# SCH__LM324_2022-09-28.net
KiCad netlist of a schematic drawn in EasyEDA
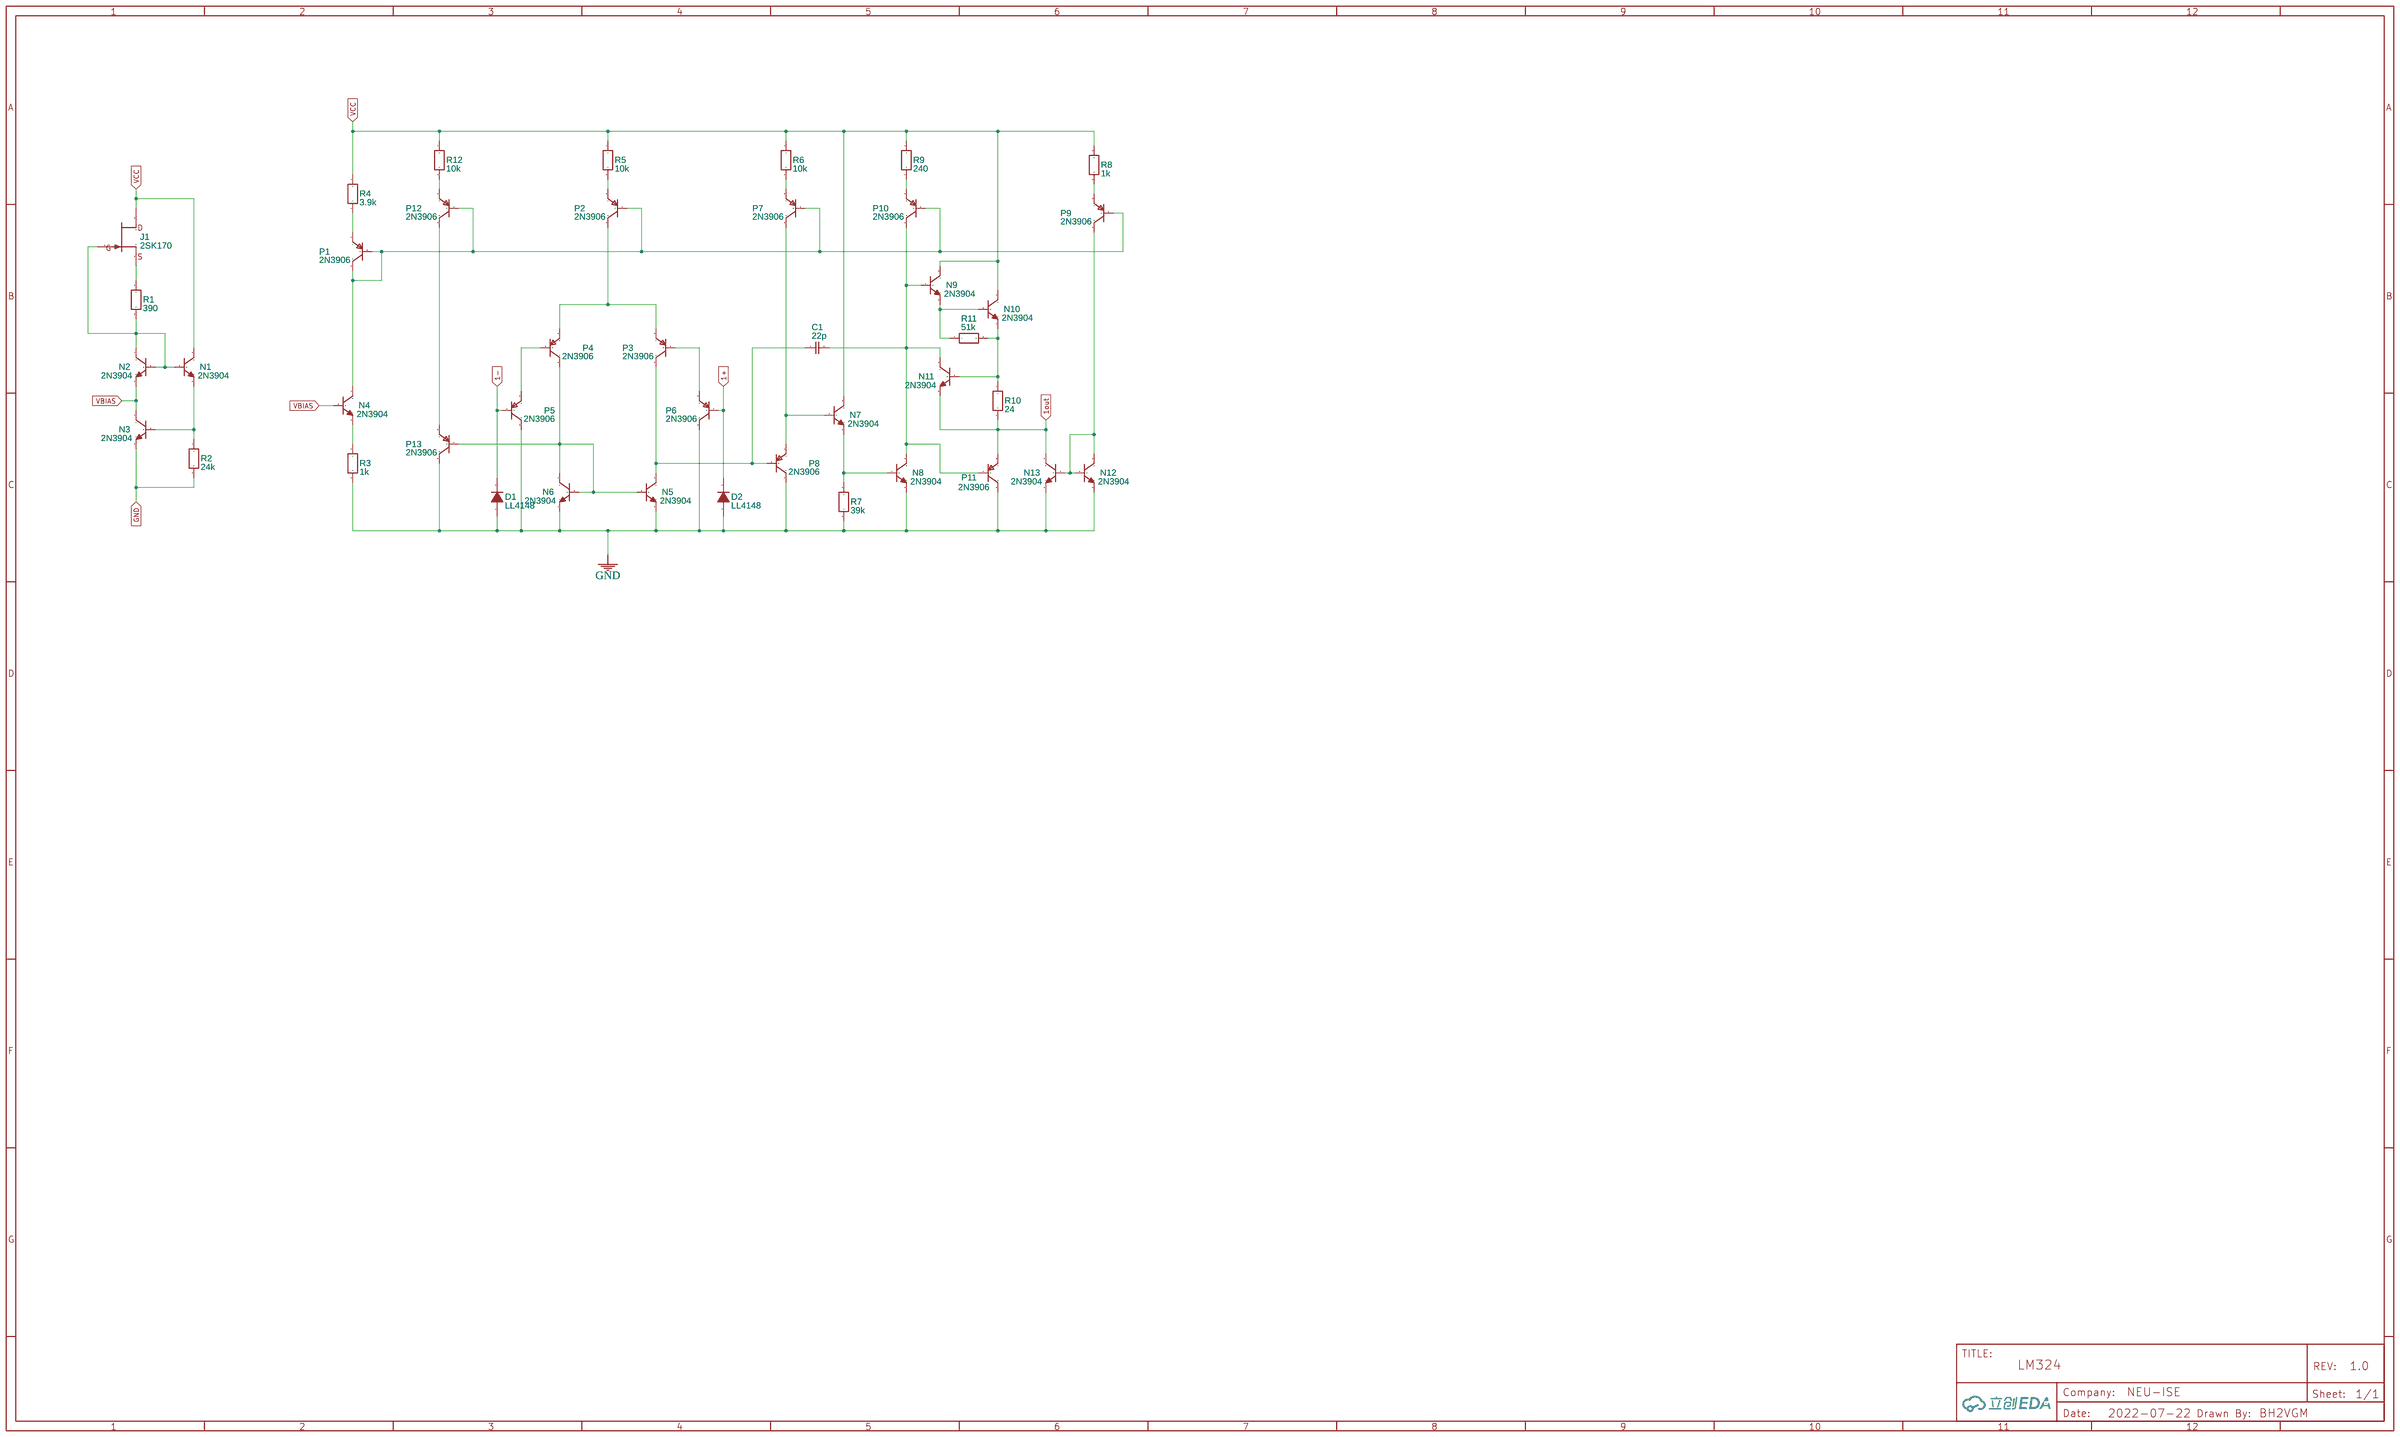
[diagram p0: schematic sheet]

(export (version "E")
  (design (tool "Eeschema 10.0.6"))
  (components
    (comp (ref "C1") (value "22p") (libsource (lib "") (part "独石电容 5.08mm")))
    (comp (ref "D1")
      (value "LL4148")
      (fields
        (field (name "BOM_Manufacturer Part") "LL4148-GS08")
        (field (name "BOM_Supplier Part") "C68883")
      )
      (libsource (lib "") (part "LL4148"))
    )
    (comp (ref "D2")
      (value "LL4148")
      (fields
        (field (name "BOM_Manufacturer Part") "LL4148-GS08")
        (field (name "BOM_Supplier Part") "C68883")
      )
      (libsource (lib "") (part "LL4148"))
    )
    (comp (ref "J1") (value "2SK170") (libsource (lib "") (part "2SK170")))
    (comp (ref "N1")
      (value "2N3904")
      (fields (field (name "BOM_Supplier Part") "C118538"))
      (libsource (lib "") (part "2N3904_1"))
    )
    (comp (ref "N2")
      (value "2N3904")
      (fields (field (name "BOM_Supplier Part") "C118538"))
      (libsource (lib "") (part "2N3904"))
    )
    (comp (ref "N3")
      (value "2N3904")
      (fields (field (name "BOM_Supplier Part") "C118538"))
      (libsource (lib "") (part "2N3904"))
    )
    (comp (ref "N4")
      (value "2N3904")
      (fields (field (name "BOM_Supplier Part") "C118538"))
      (libsource (lib "") (part "2N3904_1"))
    )
    (comp (ref "N5")
      (value "2N3904")
      (fields (field (name "BOM_Supplier Part") "C118538"))
      (libsource (lib "") (part "2N3904_1"))
    )
    (comp (ref "N6")
      (value "2N3904")
      (fields (field (name "BOM_Supplier Part") "C118538"))
      (libsource (lib "") (part "2N3904"))
    )
    (comp (ref "N7")
      (value "2N3904")
      (fields (field (name "BOM_Supplier Part") "C118538"))
      (libsource (lib "") (part "2N3904_1"))
    )
    (comp (ref "N8")
      (value "2N3904")
      (fields (field (name "BOM_Supplier Part") "C118538"))
      (libsource (lib "") (part "2N3904_1"))
    )
    (comp (ref "N9")
      (value "2N3904")
      (fields (field (name "BOM_Supplier Part") "C118538"))
      (libsource (lib "") (part "2N3904_1"))
    )
    (comp (ref "N10")
      (value "2N3904")
      (fields (field (name "BOM_Supplier Part") "C118538"))
      (libsource (lib "") (part "2N3904_1"))
    )
    (comp (ref "N11")
      (value "2N3904")
      (fields (field (name "BOM_Supplier Part") "C118538"))
      (libsource (lib "") (part "2N3904"))
    )
    (comp (ref "N12")
      (value "2N3904")
      (fields (field (name "BOM_Supplier Part") "C118538"))
      (libsource (lib "") (part "2N3904_1"))
    )
    (comp (ref "N13")
      (value "2N3904")
      (fields (field (name "BOM_Supplier Part") "C118538"))
      (libsource (lib "") (part "2N3904"))
    )
    (comp (ref "P1")
      (value "2N3906")
      (fields (field (name "BOM_Supplier Part") "C9809"))
      (libsource (lib "") (part "2N3906_1"))
    )
    (comp (ref "P2")
      (value "2N3906")
      (fields (field (name "BOM_Supplier Part") "C9809"))
      (libsource (lib "") (part "2N3906_1"))
    )
    (comp (ref "P3")
      (value "2N3906")
      (fields (field (name "BOM_Supplier Part") "C9809"))
      (libsource (lib "") (part "2N3906_1"))
    )
    (comp (ref "P4")
      (value "2N3906")
      (fields (field (name "BOM_Supplier Part") "C9809"))
      (libsource (lib "") (part "2N3906"))
    )
    (comp (ref "P5")
      (value "2N3906")
      (fields (field (name "BOM_Supplier Part") "C9809"))
      (libsource (lib "") (part "2N3906"))
    )
    (comp (ref "P6")
      (value "2N3906")
      (fields (field (name "BOM_Supplier Part") "C9809"))
      (libsource (lib "") (part "2N3906_1"))
    )
    (comp (ref "P7")
      (value "2N3906")
      (fields (field (name "BOM_Supplier Part") "C9809"))
      (libsource (lib "") (part "2N3906_1"))
    )
    (comp (ref "P8")
      (value "2N3906")
      (fields (field (name "BOM_Supplier Part") "C9809"))
      (libsource (lib "") (part "2N3906"))
    )
    (comp (ref "P9")
      (value "2N3906")
      (fields (field (name "BOM_Supplier Part") "C9809"))
      (libsource (lib "") (part "2N3906_1"))
    )
    (comp (ref "P10")
      (value "2N3906")
      (fields (field (name "BOM_Supplier Part") "C9809"))
      (libsource (lib "") (part "2N3906_1"))
    )
    (comp (ref "P11")
      (value "2N3906")
      (fields (field (name "BOM_Supplier Part") "C9809"))
      (libsource (lib "") (part "2N3906"))
    )
    (comp (ref "P12")
      (value "2N3906")
      (fields (field (name "BOM_Supplier Part") "C9809"))
      (libsource (lib "") (part "2N3906_1"))
    )
    (comp (ref "P13")
      (value "2N3906")
      (fields (field (name "BOM_Supplier Part") "C9809"))
      (libsource (lib "") (part "2N3906_1"))
    )
    (comp (ref "R1") (value "390") (libsource (lib "") (part "1/4W电阻")))
    (comp (ref "R2") (value "24k") (libsource (lib "") (part "1/4W电阻")))
    (comp (ref "R3") (value "1k") (libsource (lib "") (part "1/4W电阻")))
    (comp (ref "R4") (value "3.9k") (libsource (lib "") (part "1/4W电阻")))
    (comp (ref "R5") (value "10k") (libsource (lib "") (part "1/4W电阻")))
    (comp (ref "R6") (value "10k") (libsource (lib "") (part "1/4W电阻")))
    (comp (ref "R7") (value "39k") (libsource (lib "") (part "1/4W电阻")))
    (comp (ref "R8") (value "1k") (libsource (lib "") (part "1/4W电阻")))
    (comp (ref "R9") (value "240") (libsource (lib "") (part "1/4W电阻")))
    (comp (ref "R10") (value "24") (libsource (lib "") (part "1/4W电阻")))
    (comp (ref "R11") (value "51k") (libsource (lib "") (part "1/4W电阻_1")))
    (comp (ref "R12") (value "10k") (libsource (lib "") (part "1/4W电阻")))
  )
  (nets
    (net (code "1") (name "1+") (class "Default")
      (node (ref "D2") (pin "1") (pinfunction "C_1") (pintype "unspecified"))
      (node (ref "P6") (pin "b") (pinfunction "B_b") (pintype "unspecified"))
    )
    (net (code "2") (name "1-") (class "Default")
      (node (ref "D1") (pin "1") (pinfunction "C_1") (pintype "unspecified"))
      (node (ref "P5") (pin "b") (pinfunction "B_b") (pintype "unspecified"))
    )
    (net (code "3") (name "1out") (class "Default")
      (node (ref "N11") (pin "e") (pinfunction "E_e") (pintype "unspecified"))
      (node (ref "N13") (pin "c") (pinfunction "C_c") (pintype "unspecified"))
      (node (ref "P11") (pin "e") (pinfunction "E_e") (pintype "unspecified"))
      (node (ref "R10") (pin "2") (pinfunction "2_2") (pintype "unspecified"))
    )
    (net (code "4") (name "GND") (class "Default")
      (node (ref "D1") (pin "2") (pinfunction "A_2") (pintype "unspecified"))
      (node (ref "D2") (pin "2") (pinfunction "A_2") (pintype "unspecified"))
      (node (ref "N12") (pin "e") (pinfunction "E_e") (pintype "unspecified"))
      (node (ref "N13") (pin "e") (pinfunction "E_e") (pintype "unspecified"))
      (node (ref "N3") (pin "e") (pinfunction "E_e") (pintype "unspecified"))
      (node (ref "N5") (pin "e") (pinfunction "E_e") (pintype "unspecified"))
      (node (ref "N6") (pin "e") (pinfunction "E_e") (pintype "unspecified"))
      (node (ref "N8") (pin "e") (pinfunction "E_e") (pintype "unspecified"))
      (node (ref "P11") (pin "c") (pinfunction "C_c") (pintype "unspecified"))
      (node (ref "P13") (pin "c") (pinfunction "C_c") (pintype "unspecified"))
      (node (ref "P5") (pin "c") (pinfunction "C_c") (pintype "unspecified"))
      (node (ref "P6") (pin "c") (pinfunction "C_c") (pintype "unspecified"))
      (node (ref "P8") (pin "c") (pinfunction "C_c") (pintype "unspecified"))
      (node (ref "R2") (pin "2") (pinfunction "2_2") (pintype "unspecified"))
      (node (ref "R3") (pin "2") (pinfunction "2_2") (pintype "unspecified"))
      (node (ref "R7") (pin "2") (pinfunction "2_2") (pintype "unspecified"))
    )
    (net (code "5") (name "Net-(J1-G)") (class "Default")
      (node (ref "J1") (pin "2") (pinfunction "G_2") (pintype "unspecified"))
      (node (ref "N1") (pin "b") (pinfunction "B_b") (pintype "unspecified"))
      (node (ref "N2") (pin "b") (pinfunction "B_b") (pintype "unspecified"))
      (node (ref "N2") (pin "c") (pinfunction "C_c") (pintype "unspecified"))
      (node (ref "R1") (pin "2") (pinfunction "2_2") (pintype "unspecified"))
    )
    (net (code "6") (name "Net-(J1-S)") (class "Default")
      (node (ref "J1") (pin "1") (pinfunction "S_1") (pintype "unspecified"))
      (node (ref "R1") (pin "1") (pinfunction "1_1") (pintype "unspecified"))
    )
    (net (code "7") (name "Net-(N1-E)") (class "Default")
      (node (ref "N1") (pin "e") (pinfunction "E_e") (pintype "unspecified"))
      (node (ref "N3") (pin "b") (pinfunction "B_b") (pintype "unspecified"))
      (node (ref "R2") (pin "1") (pinfunction "1_1") (pintype "unspecified"))
    )
    (net (code "8") (name "Net-(N4-C)") (class "Default")
      (node (ref "N4") (pin "c") (pinfunction "C_c") (pintype "unspecified"))
      (node (ref "P1") (pin "b") (pinfunction "B_b") (pintype "unspecified"))
      (node (ref "P1") (pin "c") (pinfunction "C_c") (pintype "unspecified"))
      (node (ref "P10") (pin "b") (pinfunction "B_b") (pintype "unspecified"))
      (node (ref "P12") (pin "b") (pinfunction "B_b") (pintype "unspecified"))
      (node (ref "P2") (pin "b") (pinfunction "B_b") (pintype "unspecified"))
      (node (ref "P7") (pin "b") (pinfunction "B_b") (pintype "unspecified"))
      (node (ref "P9") (pin "b") (pinfunction "B_b") (pintype "unspecified"))
    )
    (net (code "9") (name "Net-(N4-E)") (class "Default")
      (node (ref "N4") (pin "e") (pinfunction "E_e") (pintype "unspecified"))
      (node (ref "R3") (pin "1") (pinfunction "1_1") (pintype "unspecified"))
    )
    (net (code "10") (name "Net-(N5-B)") (class "Default")
      (node (ref "N5") (pin "b") (pinfunction "B_b") (pintype "unspecified"))
      (node (ref "N6") (pin "b") (pinfunction "B_b") (pintype "unspecified"))
      (node (ref "N6") (pin "c") (pinfunction "C_c") (pintype "unspecified"))
      (node (ref "P13") (pin "b") (pinfunction "B_b") (pintype "unspecified"))
      (node (ref "P4") (pin "c") (pinfunction "C_c") (pintype "unspecified"))
    )
    (net (code "11") (name "Net-(N5-C)") (class "Default")
      (node (ref "C1") (pin "1") (pinfunction "1_1") (pintype "unspecified"))
      (node (ref "N5") (pin "c") (pinfunction "C_c") (pintype "unspecified"))
      (node (ref "P3") (pin "c") (pinfunction "C_c") (pintype "unspecified"))
      (node (ref "P8") (pin "b") (pinfunction "B_b") (pintype "unspecified"))
    )
    (net (code "12") (name "Net-(N7-B)") (class "Default")
      (node (ref "N7") (pin "b") (pinfunction "B_b") (pintype "unspecified"))
      (node (ref "P7") (pin "c") (pinfunction "C_c") (pintype "unspecified"))
      (node (ref "P8") (pin "e") (pinfunction "E_e") (pintype "unspecified"))
    )
    (net (code "13") (name "Net-(N7-E)") (class "Default")
      (node (ref "N7") (pin "e") (pinfunction "E_e") (pintype "unspecified"))
      (node (ref "N8") (pin "b") (pinfunction "B_b") (pintype "unspecified"))
      (node (ref "R7") (pin "1") (pinfunction "1_1") (pintype "unspecified"))
    )
    (net (code "14") (name "Net-(N10-B)") (class "Default")
      (node (ref "N10") (pin "b") (pinfunction "B_b") (pintype "unspecified"))
      (node (ref "N9") (pin "e") (pinfunction "E_e") (pintype "unspecified"))
      (node (ref "R11") (pin "1") (pinfunction "1_1") (pintype "unspecified"))
    )
    (net (code "15") (name "Net-(N10-E)") (class "Default")
      (node (ref "N10") (pin "e") (pinfunction "E_e") (pintype "unspecified"))
      (node (ref "N11") (pin "b") (pinfunction "B_b") (pintype "unspecified"))
      (node (ref "R10") (pin "1") (pinfunction "1_1") (pintype "unspecified"))
      (node (ref "R11") (pin "2") (pinfunction "2_2") (pintype "unspecified"))
    )
    (net (code "16") (name "Net-(N11-C)") (class "Default")
      (node (ref "C1") (pin "2") (pinfunction "2_2") (pintype "unspecified"))
      (node (ref "N11") (pin "c") (pinfunction "C_c") (pintype "unspecified"))
      (node (ref "N8") (pin "c") (pinfunction "C_c") (pintype "unspecified"))
      (node (ref "N9") (pin "b") (pinfunction "B_b") (pintype "unspecified"))
      (node (ref "P10") (pin "c") (pinfunction "C_c") (pintype "unspecified"))
      (node (ref "P11") (pin "b") (pinfunction "B_b") (pintype "unspecified"))
    )
    (net (code "17") (name "Net-(N12-B)") (class "Default")
      (node (ref "N12") (pin "b") (pinfunction "B_b") (pintype "unspecified"))
      (node (ref "N12") (pin "c") (pinfunction "C_c") (pintype "unspecified"))
      (node (ref "N13") (pin "b") (pinfunction "B_b") (pintype "unspecified"))
      (node (ref "P9") (pin "c") (pinfunction "C_c") (pintype "unspecified"))
    )
    (net (code "18") (name "Net-(P1-E)") (class "Default")
      (node (ref "P1") (pin "e") (pinfunction "E_e") (pintype "unspecified"))
      (node (ref "R4") (pin "2") (pinfunction "2_2") (pintype "unspecified"))
    )
    (net (code "19") (name "Net-(P2-C)") (class "Default")
      (node (ref "P2") (pin "c") (pinfunction "C_c") (pintype "unspecified"))
      (node (ref "P3") (pin "e") (pinfunction "E_e") (pintype "unspecified"))
      (node (ref "P4") (pin "e") (pinfunction "E_e") (pintype "unspecified"))
    )
    (net (code "20") (name "Net-(P2-E)") (class "Default")
      (node (ref "P2") (pin "e") (pinfunction "E_e") (pintype "unspecified"))
      (node (ref "R5") (pin "2") (pinfunction "2_2") (pintype "unspecified"))
    )
    (net (code "21") (name "Net-(P3-B)") (class "Default")
      (node (ref "P3") (pin "b") (pinfunction "B_b") (pintype "unspecified"))
      (node (ref "P6") (pin "e") (pinfunction "E_e") (pintype "unspecified"))
    )
    (net (code "22") (name "Net-(P4-B)") (class "Default")
      (node (ref "P4") (pin "b") (pinfunction "B_b") (pintype "unspecified"))
      (node (ref "P5") (pin "e") (pinfunction "E_e") (pintype "unspecified"))
    )
    (net (code "23") (name "Net-(P7-E)") (class "Default")
      (node (ref "P7") (pin "e") (pinfunction "E_e") (pintype "unspecified"))
      (node (ref "R6") (pin "2") (pinfunction "2_2") (pintype "unspecified"))
    )
    (net (code "24") (name "Net-(P9-E)") (class "Default")
      (node (ref "P9") (pin "e") (pinfunction "E_e") (pintype "unspecified"))
      (node (ref "R8") (pin "2") (pinfunction "2_2") (pintype "unspecified"))
    )
    (net (code "25") (name "Net-(P10-E)") (class "Default")
      (node (ref "P10") (pin "e") (pinfunction "E_e") (pintype "unspecified"))
      (node (ref "R9") (pin "2") (pinfunction "2_2") (pintype "unspecified"))
    )
    (net (code "26") (name "Net-(P12-C)") (class "Default")
      (node (ref "P12") (pin "c") (pinfunction "C_c") (pintype "unspecified"))
      (node (ref "P13") (pin "e") (pinfunction "E_e") (pintype "unspecified"))
    )
    (net (code "27") (name "Net-(P12-E)") (class "Default")
      (node (ref "P12") (pin "e") (pinfunction "E_e") (pintype "unspecified"))
      (node (ref "R12") (pin "2") (pinfunction "2_2") (pintype "unspecified"))
    )
    (net (code "28") (name "VBIAS") (class "Default")
      (node (ref "N2") (pin "e") (pinfunction "E_e") (pintype "unspecified"))
      (node (ref "N3") (pin "c") (pinfunction "C_c") (pintype "unspecified"))
      (node (ref "N4") (pin "b") (pinfunction "B_b") (pintype "unspecified"))
    )
    (net (code "29") (name "VCC") (class "Default")
      (node (ref "J1") (pin "3") (pinfunction "D_3") (pintype "unspecified"))
      (node (ref "N1") (pin "c") (pinfunction "C_c") (pintype "unspecified"))
      (node (ref "N10") (pin "c") (pinfunction "C_c") (pintype "unspecified"))
      (node (ref "N7") (pin "c") (pinfunction "C_c") (pintype "unspecified"))
      (node (ref "N9") (pin "c") (pinfunction "C_c") (pintype "unspecified"))
      (node (ref "R12") (pin "1") (pinfunction "1_1") (pintype "unspecified"))
      (node (ref "R4") (pin "1") (pinfunction "1_1") (pintype "unspecified"))
      (node (ref "R5") (pin "1") (pinfunction "1_1") (pintype "unspecified"))
      (node (ref "R6") (pin "1") (pinfunction "1_1") (pintype "unspecified"))
      (node (ref "R8") (pin "1") (pinfunction "1_1") (pintype "unspecified"))
      (node (ref "R9") (pin "1") (pinfunction "1_1") (pintype "unspecified"))
    )
  )
)
